# Sheet1.net
KiCad netlist of a schematic drawn in Altium Designer
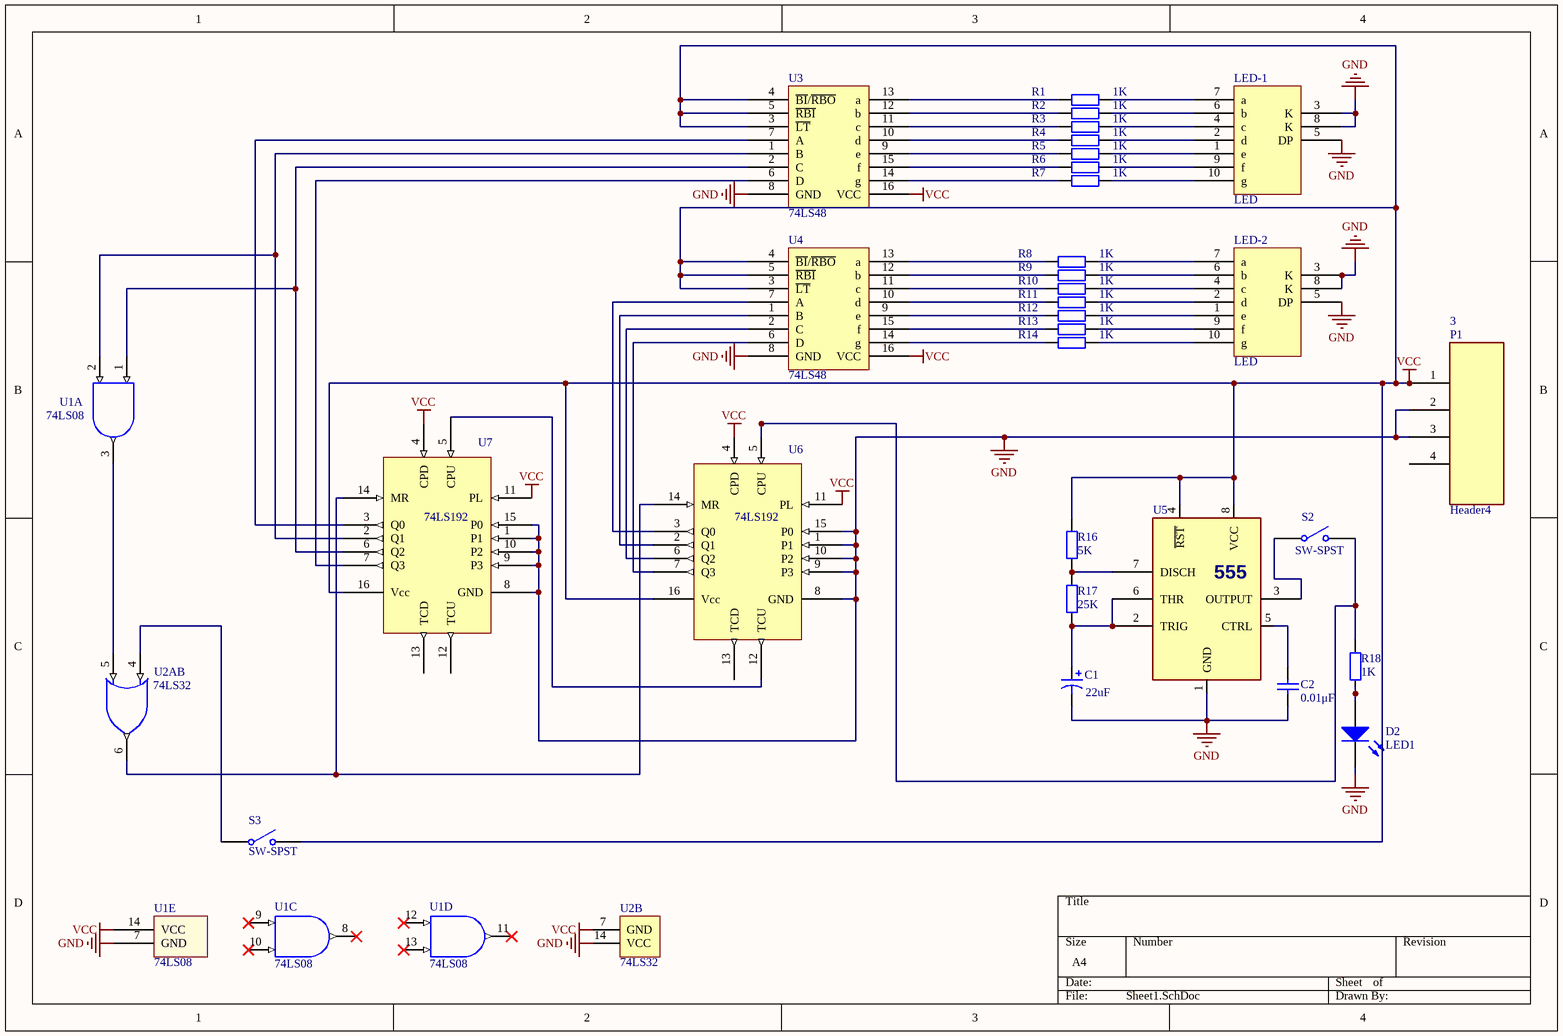
[diagram p0: Sheet1.SchDoc]

(export (version "E")
  (design (tool "Eeschema 10.0.6"))
  (components
    (comp (ref "3")
      (value "~")
      (footprint "SIP4")
      (description "555 Timer, General-Purpose Single Bipolar Timer")
      (fields (field (name "MANF_P#") "NE555P, NE555PE4") (field (name "MANF") "Texas Instruments"))
      (libsource (lib "") (part "NE555_DIP8_1"))
    )
    (comp (ref "C1")
      (value "22uF")
      (footprint "RB.2/.4")
      (description "Polarized Capacitor (Radial)")
      (fields (field (name "Comment") "Cap Pol1") (field (name "PUBLISHER") "Altium Limited"))
      (libsource (lib "Miscellaneous Devices") (part "Cap Pol1"))
    )
    (comp (ref "C2")
      (value "0.01μF")
      (footprint "RAD0.2")
      (description "Capacitor")
      (fields (field (name "PUBLISHER") "Altium Limited"))
      (libsource (lib "Miscellaneous Devices") (part "Cap"))
    )
    (comp (ref "D2")
      (value "LED1")
      (footprint "RAD0.1")
      (description "Typical RED GaAs LED")
      (fields (field (name "PUBLISHER") "Altium Limited"))
      (libsource (lib "Miscellaneous Devices") (part "LED1"))
    )
    (comp (ref "LED-1")
      (value "LED")
      (footprint "DPY_10-SEG_DP(LED)")
      (libsource (lib "Schlib1") (part "LED"))
    )
    (comp (ref "LED-2")
      (value "LED")
      (footprint "DPY_10-SEG_DP(LED)")
      (libsource (lib "Schlib1") (part "LED"))
    )
    (comp (ref "R1")
      (value "1K")
      (footprint "AXIAL-0.4")
      (description "Resistor")
      (fields (field (name "PUBLISHER") "Altium Limited"))
      (libsource (lib "Miscellaneous Devices") (part "Res2"))
    )
    (comp (ref "R2")
      (value "1K")
      (footprint "AXIAL-0.4")
      (description "Resistor")
      (fields (field (name "PUBLISHER") "Altium Limited"))
      (libsource (lib "Miscellaneous Devices") (part "Res2"))
    )
    (comp (ref "R3")
      (value "1K")
      (footprint "AXIAL-0.4")
      (description "Resistor")
      (fields (field (name "PUBLISHER") "Altium Limited"))
      (libsource (lib "Miscellaneous Devices") (part "Res2"))
    )
    (comp (ref "R4")
      (value "1K")
      (footprint "AXIAL-0.4")
      (description "Resistor")
      (fields (field (name "PUBLISHER") "Altium Limited"))
      (libsource (lib "Miscellaneous Devices") (part "Res2"))
    )
    (comp (ref "R5")
      (value "1K")
      (footprint "AXIAL-0.4")
      (description "Resistor")
      (fields (field (name "PUBLISHER") "Altium Limited"))
      (libsource (lib "Miscellaneous Devices") (part "Res2"))
    )
    (comp (ref "R6")
      (value "1K")
      (footprint "AXIAL-0.4")
      (description "Resistor")
      (fields (field (name "PUBLISHER") "Altium Limited"))
      (libsource (lib "Miscellaneous Devices") (part "Res2"))
    )
    (comp (ref "R7")
      (value "1K")
      (footprint "AXIAL-0.4")
      (description "Resistor")
      (fields (field (name "PUBLISHER") "Altium Limited"))
      (libsource (lib "Miscellaneous Devices") (part "Res2"))
    )
    (comp (ref "R8")
      (value "1K")
      (footprint "AXIAL-0.4")
      (description "Resistor")
      (fields (field (name "PUBLISHER") "Altium Limited"))
      (libsource (lib "Miscellaneous Devices") (part "Res2"))
    )
    (comp (ref "R9")
      (value "1K")
      (footprint "AXIAL-0.4")
      (description "Resistor")
      (fields (field (name "PUBLISHER") "Altium Limited"))
      (libsource (lib "Miscellaneous Devices") (part "Res2"))
    )
    (comp (ref "R10")
      (value "1K")
      (footprint "AXIAL-0.4")
      (description "Resistor")
      (fields (field (name "PUBLISHER") "Altium Limited"))
      (libsource (lib "Miscellaneous Devices") (part "Res2"))
    )
    (comp (ref "R11")
      (value "1K")
      (footprint "AXIAL-0.4")
      (description "Resistor")
      (fields (field (name "PUBLISHER") "Altium Limited"))
      (libsource (lib "Miscellaneous Devices") (part "Res2"))
    )
    (comp (ref "R12")
      (value "1K")
      (footprint "AXIAL-0.4")
      (description "Resistor")
      (fields (field (name "PUBLISHER") "Altium Limited"))
      (libsource (lib "Miscellaneous Devices") (part "Res2"))
    )
    (comp (ref "R13")
      (value "1K")
      (footprint "AXIAL-0.4")
      (description "Resistor")
      (fields (field (name "PUBLISHER") "Altium Limited"))
      (libsource (lib "Miscellaneous Devices") (part "Res2"))
    )
    (comp (ref "R14")
      (value "1K")
      (footprint "AXIAL-0.4")
      (description "Resistor")
      (fields (field (name "PUBLISHER") "Altium Limited"))
      (libsource (lib "Miscellaneous Devices") (part "Res2"))
    )
    (comp (ref "R16")
      (value "5K")
      (footprint "AXIAL-0.4")
      (description "Resistor")
      (fields (field (name "PUBLISHER") "Altium Limited"))
      (libsource (lib "") (part "Res2_1"))
    )
    (comp (ref "R17")
      (value "25K")
      (footprint "AXIAL-0.4")
      (description "Resistor")
      (fields (field (name "PUBLISHER") "Altium Limited"))
      (libsource (lib "") (part "Res2_1"))
    )
    (comp (ref "R18")
      (value "1K")
      (footprint "AXIAL-0.4")
      (description "Resistor")
      (fields (field (name "PUBLISHER") "Altium Limited"))
      (libsource (lib "") (part "Res2_2"))
    )
    (comp (ref "S2")
      (value "SW-SPST")
      (footprint "SIP3")
      (description "Single-Pole, Single-Throw Switch")
      (fields (field (name "PUBLISHER") "Altium Limited"))
      (libsource (lib "Miscellaneous Devices") (part "SW-SPST"))
    )
    (comp (ref "S3")
      (value "SW-SPST")
      (footprint "SIP3")
      (description "Single-Pole, Single-Throw Switch")
      (fields (field (name "PUBLISHER") "Altium Limited"))
      (libsource (lib "Miscellaneous Devices") (part "SW-SPST"))
    )
    (comp (ref "U1")
      (value "74LS08")
      (footprint "DIP-14")
      (description "Quad 2-Input Positive-AND Gate")
      (libsource (lib "") (part "74LS08_1"))
    )
    (comp (ref "U2A")
      (value "74LS32")
      (footprint "DIP-14")
      (description "Quadruple 2-Input Positive-OR Gate")
      (fields (field (name "PUBLISHER") "Altium Limited"))
      (libsource (lib "Schlib1") (part "SN74F32D"))
    )
    (comp (ref "U2B")
      (value "74LS32")
      (footprint "DIP-14")
      (fields (field (name "PUBLISHER") "Altium Limited"))
      (libsource (lib "Miscellaneous Connectors") (part "Header 2"))
    )
    (comp (ref "U3") (value "74LS48") (footprint "DIP-16") (libsource (lib "PCB_Project") (part "74LS48")))
    (comp (ref "U4") (value "74LS48") (footprint "DIP-16") (libsource (lib "PCB_Project") (part "74LS48")))
    (comp (ref "U5")
      (value "~")
      (footprint "DIP-8")
      (description "555 Timer, General-Purpose Single Bipolar Timer")
      (fields (field (name "MANF_P#") "NE555P, NE555PE4") (field (name "MANF") "Texas Instruments"))
      (libsource (lib "ne555") (part "NE555_DIP8"))
    )
    (comp (ref "U6") (value "74LS192") (footprint "DIP-16") (libsource (lib "sw") (part "74LS192")))
    (comp (ref "U7") (value "74LS192") (footprint "DIP-16") (libsource (lib "sw") (part "74LS192")))
  )
  (nets
    (net (code "1") (name "GND") (class "Default")
      (node (ref "3") (pin "2") (pintype "passive"))
      (node (ref "3") (pin "3") (pintype "passive"))
      (node (ref "C1") (pin "2") (pinfunction "2_2") (pintype "passive"))
      (node (ref "C2") (pin "1") (pinfunction "1_1") (pintype "passive"))
      (node (ref "D2") (pin "2") (pinfunction "K_2") (pintype "passive"))
      (node (ref "LED-1") (pin "3") (pinfunction "K_3") (pintype "passive"))
      (node (ref "LED-1") (pin "5") (pinfunction "DP_5") (pintype "passive"))
      (node (ref "LED-1") (pin "8") (pinfunction "K_8") (pintype "passive"))
      (node (ref "LED-2") (pin "3") (pinfunction "K_3") (pintype "passive"))
      (node (ref "LED-2") (pin "5") (pinfunction "DP_5") (pintype "passive"))
      (node (ref "LED-2") (pin "8") (pinfunction "K_8") (pintype "passive"))
      (node (ref "U1") (pin "7") (pinfunction "GND_7") (pintype "power_in"))
      (node (ref "U2A") (pin "7") (pinfunction "GND_7") (pintype "power_in"))
      (node (ref "U2B") (pin "14") (pinfunction "VCC_14") (pintype "passive"))
      (node (ref "U3") (pin "8") (pinfunction "GND_8") (pintype "passive"))
      (node (ref "U4") (pin "8") (pinfunction "GND_8") (pintype "passive"))
      (node (ref "U5") (pin "1") (pinfunction "GND_1") (pintype "passive"))
      (node (ref "U6") (pin "1") (pinfunction "P1_1") (pintype "input"))
      (node (ref "U6") (pin "10") (pinfunction "P2_10") (pintype "input"))
      (node (ref "U6") (pin "15") (pinfunction "P0_15") (pintype "input"))
      (node (ref "U6") (pin "8") (pinfunction "GND_8") (pintype "passive"))
      (node (ref "U6") (pin "9") (pinfunction "P3_9") (pintype "input"))
      (node (ref "U7") (pin "1") (pinfunction "P1_1") (pintype "input"))
      (node (ref "U7") (pin "10") (pinfunction "P2_10") (pintype "input"))
      (node (ref "U7") (pin "15") (pinfunction "P0_15") (pintype "input"))
      (node (ref "U7") (pin "8") (pinfunction "GND_8") (pintype "passive"))
      (node (ref "U7") (pin "9") (pinfunction "P3_9") (pintype "input"))
    )
    (net (code "2") (name "Net-(D2-A)") (class "Default")
      (node (ref "D2") (pin "1") (pinfunction "A_1") (pintype "passive"))
      (node (ref "R18") (pin "2") (pinfunction "2_2") (pintype "passive"))
    )
    (net (code "3") (name "Net-(LED-1-a)") (class "Default")
      (node (ref "LED-1") (pin "7") (pinfunction "a_7") (pintype "passive"))
      (node (ref "R1") (pin "1") (pinfunction "1_1") (pintype "passive"))
    )
    (net (code "4") (name "Net-(LED-1-b)") (class "Default")
      (node (ref "LED-1") (pin "6") (pinfunction "b_6") (pintype "passive"))
      (node (ref "R2") (pin "1") (pinfunction "1_1") (pintype "passive"))
    )
    (net (code "5") (name "Net-(LED-1-c)") (class "Default")
      (node (ref "LED-1") (pin "4") (pinfunction "c_4") (pintype "passive"))
      (node (ref "R3") (pin "1") (pinfunction "1_1") (pintype "passive"))
    )
    (net (code "6") (name "Net-(LED-1-d)") (class "Default")
      (node (ref "LED-1") (pin "2") (pinfunction "d_2") (pintype "passive"))
      (node (ref "R4") (pin "1") (pinfunction "1_1") (pintype "passive"))
    )
    (net (code "7") (name "Net-(LED-1-e)") (class "Default")
      (node (ref "LED-1") (pin "1") (pinfunction "e_1") (pintype "passive"))
      (node (ref "R5") (pin "1") (pinfunction "1_1") (pintype "passive"))
    )
    (net (code "8") (name "Net-(LED-1-f)") (class "Default")
      (node (ref "LED-1") (pin "9") (pinfunction "f_9") (pintype "passive"))
      (node (ref "R6") (pin "1") (pinfunction "1_1") (pintype "passive"))
    )
    (net (code "9") (name "Net-(LED-1-g)") (class "Default")
      (node (ref "LED-1") (pin "10") (pinfunction "g_10") (pintype "passive"))
      (node (ref "R7") (pin "1") (pinfunction "1_1") (pintype "passive"))
    )
    (net (code "10") (name "Net-(LED-2-a)") (class "Default")
      (node (ref "LED-2") (pin "7") (pinfunction "a_7") (pintype "passive"))
      (node (ref "R8") (pin "1") (pinfunction "1_1") (pintype "passive"))
    )
    (net (code "11") (name "Net-(LED-2-b)") (class "Default")
      (node (ref "LED-2") (pin "6") (pinfunction "b_6") (pintype "passive"))
      (node (ref "R9") (pin "1") (pinfunction "1_1") (pintype "passive"))
    )
    (net (code "12") (name "Net-(LED-2-c)") (class "Default")
      (node (ref "LED-2") (pin "4") (pinfunction "c_4") (pintype "passive"))
      (node (ref "R10") (pin "1") (pinfunction "1_1") (pintype "passive"))
    )
    (net (code "13") (name "Net-(LED-2-d)") (class "Default")
      (node (ref "LED-2") (pin "2") (pinfunction "d_2") (pintype "passive"))
      (node (ref "R11") (pin "1") (pinfunction "1_1") (pintype "passive"))
    )
    (net (code "14") (name "Net-(LED-2-e)") (class "Default")
      (node (ref "LED-2") (pin "1") (pinfunction "e_1") (pintype "passive"))
      (node (ref "R12") (pin "1") (pinfunction "1_1") (pintype "passive"))
    )
    (net (code "15") (name "Net-(LED-2-f)") (class "Default")
      (node (ref "LED-2") (pin "9") (pinfunction "f_9") (pintype "passive"))
      (node (ref "R13") (pin "1") (pinfunction "1_1") (pintype "passive"))
    )
    (net (code "16") (name "Net-(LED-2-g)") (class "Default")
      (node (ref "LED-2") (pin "10") (pinfunction "g_10") (pintype "passive"))
      (node (ref "R14") (pin "1") (pinfunction "1_1") (pintype "passive"))
    )
    (net (code "17") (name "Net-(S2-COMMON)") (class "Default")
      (node (ref "S2") (pin "1") (pinfunction "COMMON_1") (pintype "passive"))
      (node (ref "U5") (pin "3") (pinfunction "OUTPUT_3") (pintype "passive"))
    )
    (net (code "18") (name "Net-(S2-NO)") (class "Default")
      (node (ref "R18") (pin "1") (pinfunction "1_1") (pintype "passive"))
      (node (ref "S2") (pin "2") (pinfunction "NO_2") (pintype "passive"))
      (node (ref "U6") (pin "5") (pinfunction "CPU_5") (pintype "input"))
    )
    (net (code "19") (name "Net-(S3-COMMON)") (class "Default")
      (node (ref "S3") (pin "1") (pinfunction "COMMON_1") (pintype "passive"))
      (node (ref "U2A") (pin "4") (pinfunction "A_4") (pintype "input"))
    )
    (net (code "20") (name "Net-(U1A-A)") (class "Default")
      (node (ref "U1") (pin "1") (pinfunction "A_1") (pintype "input"))
      (node (ref "U3") (pin "2") (pinfunction "C_2") (pintype "passive"))
      (node (ref "U7") (pin "6") (pinfunction "Q2_6") (pintype "output"))
    )
    (net (code "21") (name "Net-(U1A-B)") (class "Default")
      (node (ref "U1") (pin "2") (pinfunction "B_2") (pintype "input"))
      (node (ref "U3") (pin "1") (pinfunction "B_1") (pintype "passive"))
      (node (ref "U7") (pin "2") (pinfunction "Q1_2") (pintype "output"))
    )
    (net (code "22") (name "Net-(U1A-Y)") (class "Default")
      (node (ref "U1") (pin "3") (pinfunction "Y_3") (pintype "output"))
      (node (ref "U2A") (pin "5") (pinfunction "B_5") (pintype "input"))
    )
    (net (code "23") (name "Net-(U2AB-Y)") (class "Default")
      (node (ref "U2A") (pin "6") (pinfunction "Y_6") (pintype "output"))
      (node (ref "U6") (pin "14") (pinfunction "MR_14") (pintype "input"))
      (node (ref "U7") (pin "14") (pinfunction "MR_14") (pintype "input"))
    )
    (net (code "24") (name "Net-(U3-A)") (class "Default")
      (node (ref "U3") (pin "7") (pinfunction "A_7") (pintype "passive"))
      (node (ref "U7") (pin "3") (pinfunction "Q0_3") (pintype "output"))
    )
    (net (code "25") (name "Net-(U3-D)") (class "Default")
      (node (ref "U3") (pin "6") (pinfunction "D_6") (pintype "passive"))
      (node (ref "U7") (pin "7") (pinfunction "Q3_7") (pintype "output"))
    )
    (net (code "26") (name "Net-(U3-a)") (class "Default")
      (node (ref "R1") (pin "2") (pinfunction "2_2") (pintype "passive"))
      (node (ref "U3") (pin "13") (pinfunction "a_13") (pintype "passive"))
    )
    (net (code "27") (name "Net-(U3-b)") (class "Default")
      (node (ref "R2") (pin "2") (pinfunction "2_2") (pintype "passive"))
      (node (ref "U3") (pin "12") (pinfunction "b_12") (pintype "passive"))
    )
    (net (code "28") (name "Net-(U3-c)") (class "Default")
      (node (ref "R3") (pin "2") (pinfunction "2_2") (pintype "passive"))
      (node (ref "U3") (pin "11") (pinfunction "c_11") (pintype "passive"))
    )
    (net (code "29") (name "Net-(U3-d)") (class "Default")
      (node (ref "R4") (pin "2") (pinfunction "2_2") (pintype "passive"))
      (node (ref "U3") (pin "10") (pinfunction "d_10") (pintype "passive"))
    )
    (net (code "30") (name "Net-(U3-e)") (class "Default")
      (node (ref "R5") (pin "2") (pinfunction "2_2") (pintype "passive"))
      (node (ref "U3") (pin "9") (pinfunction "e_9") (pintype "passive"))
    )
    (net (code "31") (name "Net-(U3-f)") (class "Default")
      (node (ref "R6") (pin "2") (pinfunction "2_2") (pintype "passive"))
      (node (ref "U3") (pin "15") (pinfunction "f_15") (pintype "passive"))
    )
    (net (code "32") (name "Net-(U3-g)") (class "Default")
      (node (ref "R7") (pin "2") (pinfunction "2_2") (pintype "passive"))
      (node (ref "U3") (pin "14") (pinfunction "g_14") (pintype "passive"))
    )
    (net (code "33") (name "Net-(U4-A)") (class "Default")
      (node (ref "U4") (pin "7") (pinfunction "A_7") (pintype "passive"))
      (node (ref "U6") (pin "3") (pinfunction "Q0_3") (pintype "output"))
    )
    (net (code "34") (name "Net-(U4-B)") (class "Default")
      (node (ref "U4") (pin "1") (pinfunction "B_1") (pintype "passive"))
      (node (ref "U6") (pin "2") (pinfunction "Q1_2") (pintype "output"))
    )
    (net (code "35") (name "Net-(U4-C)") (class "Default")
      (node (ref "U4") (pin "2") (pinfunction "C_2") (pintype "passive"))
      (node (ref "U6") (pin "6") (pinfunction "Q2_6") (pintype "output"))
    )
    (net (code "36") (name "Net-(U4-D)") (class "Default")
      (node (ref "U4") (pin "6") (pinfunction "D_6") (pintype "passive"))
      (node (ref "U6") (pin "7") (pinfunction "Q3_7") (pintype "output"))
    )
    (net (code "37") (name "Net-(U4-a)") (class "Default")
      (node (ref "R8") (pin "2") (pinfunction "2_2") (pintype "passive"))
      (node (ref "U4") (pin "13") (pinfunction "a_13") (pintype "passive"))
    )
    (net (code "38") (name "Net-(U4-b)") (class "Default")
      (node (ref "R9") (pin "2") (pinfunction "2_2") (pintype "passive"))
      (node (ref "U4") (pin "12") (pinfunction "b_12") (pintype "passive"))
    )
    (net (code "39") (name "Net-(U4-c)") (class "Default")
      (node (ref "R10") (pin "2") (pinfunction "2_2") (pintype "passive"))
      (node (ref "U4") (pin "11") (pinfunction "c_11") (pintype "passive"))
    )
    (net (code "40") (name "Net-(U4-d)") (class "Default")
      (node (ref "R11") (pin "2") (pinfunction "2_2") (pintype "passive"))
      (node (ref "U4") (pin "10") (pinfunction "d_10") (pintype "passive"))
    )
    (net (code "41") (name "Net-(U4-e)") (class "Default")
      (node (ref "R12") (pin "2") (pinfunction "2_2") (pintype "passive"))
      (node (ref "U4") (pin "9") (pinfunction "e_9") (pintype "passive"))
    )
    (net (code "42") (name "Net-(U4-f)") (class "Default")
      (node (ref "R13") (pin "2") (pinfunction "2_2") (pintype "passive"))
      (node (ref "U4") (pin "15") (pinfunction "f_15") (pintype "passive"))
    )
    (net (code "43") (name "Net-(U4-g)") (class "Default")
      (node (ref "R14") (pin "2") (pinfunction "2_2") (pintype "passive"))
      (node (ref "U4") (pin "14") (pinfunction "g_14") (pintype "passive"))
    )
    (net (code "44") (name "Net-(U5-CTRL)") (class "Default")
      (node (ref "C2") (pin "2") (pinfunction "2_2") (pintype "passive"))
      (node (ref "U5") (pin "5") (pinfunction "CTRL_5") (pintype "passive"))
    )
    (net (code "45") (name "Net-(U5-DISCH)") (class "Default")
      (node (ref "R16") (pin "1") (pinfunction "1_1") (pintype "passive"))
      (node (ref "R17") (pin "2") (pinfunction "2_2") (pintype "passive"))
      (node (ref "U5") (pin "7") (pinfunction "DISCH_7") (pintype "passive"))
    )
    (net (code "46") (name "Net-(U5-THR)") (class "Default")
      (node (ref "C1") (pin "1") (pinfunction "1_1") (pintype "passive"))
      (node (ref "R17") (pin "1") (pinfunction "1_1") (pintype "passive"))
      (node (ref "U5") (pin "2") (pinfunction "TRIG_2") (pintype "passive"))
      (node (ref "U5") (pin "6") (pinfunction "THR_6") (pintype "passive"))
    )
    (net (code "47") (name "Net-(U6-TCU)") (class "Default")
      (node (ref "U6") (pin "12") (pinfunction "TCU_12") (pintype "output"))
      (node (ref "U7") (pin "5") (pinfunction "CPU_5") (pintype "input"))
    )
    (net (code "48") (name "VCC") (class "Default")
      (node (ref "3") (pin "1") (pintype "passive"))
      (node (ref "R16") (pin "2") (pinfunction "2_2") (pintype "passive"))
      (node (ref "S3") (pin "2") (pinfunction "NO_2") (pintype "passive"))
      (node (ref "U1") (pin "14") (pinfunction "VCC_14") (pintype "power_in"))
      (node (ref "U2A") (pin "14") (pinfunction "VCC_14") (pintype "power_in"))
      (node (ref "U2B") (pin "7") (pinfunction "GND_7") (pintype "passive"))
      (node (ref "U3") (pin "16") (pinfunction "VCC_16") (pintype "passive"))
      (node (ref "U3") (pin "3") (pinfunction "~{LT}_3") (pintype "passive"))
      (node (ref "U3") (pin "4") (pinfunction "~{BI}/~{RBO}_4") (pintype "passive"))
      (node (ref "U3") (pin "5") (pinfunction "~{RBI}_5") (pintype "passive"))
      (node (ref "U4") (pin "16") (pinfunction "VCC_16") (pintype "passive"))
      (node (ref "U4") (pin "3") (pinfunction "~{LT}_3") (pintype "passive"))
      (node (ref "U4") (pin "4") (pinfunction "~{BI}/~{RBO}_4") (pintype "passive"))
      (node (ref "U4") (pin "5") (pinfunction "~{RBI}_5") (pintype "passive"))
      (node (ref "U5") (pin "4") (pinfunction "~{RST}_4") (pintype "passive"))
      (node (ref "U5") (pin "8") (pinfunction "VCC_8") (pintype "passive"))
      (node (ref "U6") (pin "11") (pinfunction "PL_11") (pintype "input"))
      (node (ref "U6") (pin "16") (pinfunction "Vcc_16") (pintype "passive"))
      (node (ref "U7") (pin "11") (pinfunction "PL_11") (pintype "input"))
      (node (ref "U7") (pin "16") (pinfunction "Vcc_16") (pintype "passive"))
    )
    (net (code "49") (name "unconnected-(3-Pad4)") (class "Default")
      (node (ref "3") (pin "4") (pintype "passive"))
    )
    (net (code "50") (name "unconnected-(U1C-A-Pad9)") (class "Default")
      (node (ref "U1") (pin "9") (pinfunction "A_9") (pintype "input+no_connect"))
    )
    (net (code "51") (name "unconnected-(U1C-B-Pad10)") (class "Default")
      (node (ref "U1") (pin "10") (pinfunction "B_10") (pintype "input+no_connect"))
    )
    (net (code "52") (name "unconnected-(U1C-Y-Pad8)") (class "Default")
      (node (ref "U1") (pin "8") (pinfunction "Y_8") (pintype "output+no_connect"))
    )
    (net (code "53") (name "unconnected-(U1D-A-Pad12)") (class "Default")
      (node (ref "U1") (pin "12") (pinfunction "A_12") (pintype "input+no_connect"))
    )
    (net (code "54") (name "unconnected-(U1D-B-Pad13)") (class "Default")
      (node (ref "U1") (pin "13") (pinfunction "B_13") (pintype "input+no_connect"))
    )
    (net (code "55") (name "unconnected-(U1D-Y-Pad11)") (class "Default")
      (node (ref "U1") (pin "11") (pinfunction "Y_11") (pintype "output+no_connect"))
    )
    (net (code "56") (name "unconnected-(U3-Pad8)") (class "Default")
      (node (ref "U3") (pin "8") (pinfunction "8_8") (pintype "passive"))
    )
    (net (code "57") (name "unconnected-(U3-Pad16)") (class "Default")
      (node (ref "U3") (pin "16") (pinfunction "16_16") (pintype "passive"))
    )
    (net (code "58") (name "unconnected-(U4-Pad8)") (class "Default")
      (node (ref "U4") (pin "8") (pinfunction "8_8") (pintype "passive"))
    )
    (net (code "59") (name "unconnected-(U4-Pad16)") (class "Default")
      (node (ref "U4") (pin "16") (pinfunction "16_16") (pintype "passive"))
    )
    (net (code "60") (name "unconnected-(U6-CPD-Pad4)") (class "Default")
      (node (ref "U6") (pin "4") (pinfunction "CPD_4") (pintype "input"))
    )
    (net (code "61") (name "unconnected-(U6-TCD-Pad13)") (class "Default")
      (node (ref "U6") (pin "13") (pinfunction "TCD_13") (pintype "output"))
    )
    (net (code "62") (name "unconnected-(U7-CPD-Pad4)") (class "Default")
      (node (ref "U7") (pin "4") (pinfunction "CPD_4") (pintype "input"))
    )
    (net (code "63") (name "unconnected-(U7-TCD-Pad13)") (class "Default")
      (node (ref "U7") (pin "13") (pinfunction "TCD_13") (pintype "output"))
    )
    (net (code "64") (name "unconnected-(U7-TCU-Pad12)") (class "Default")
      (node (ref "U7") (pin "12") (pinfunction "TCU_12") (pintype "output"))
    )
  )
)
